# SCH_Arduino_Uno_2023-09-05.net
KiCad netlist of a schematic drawn in EasyEDA
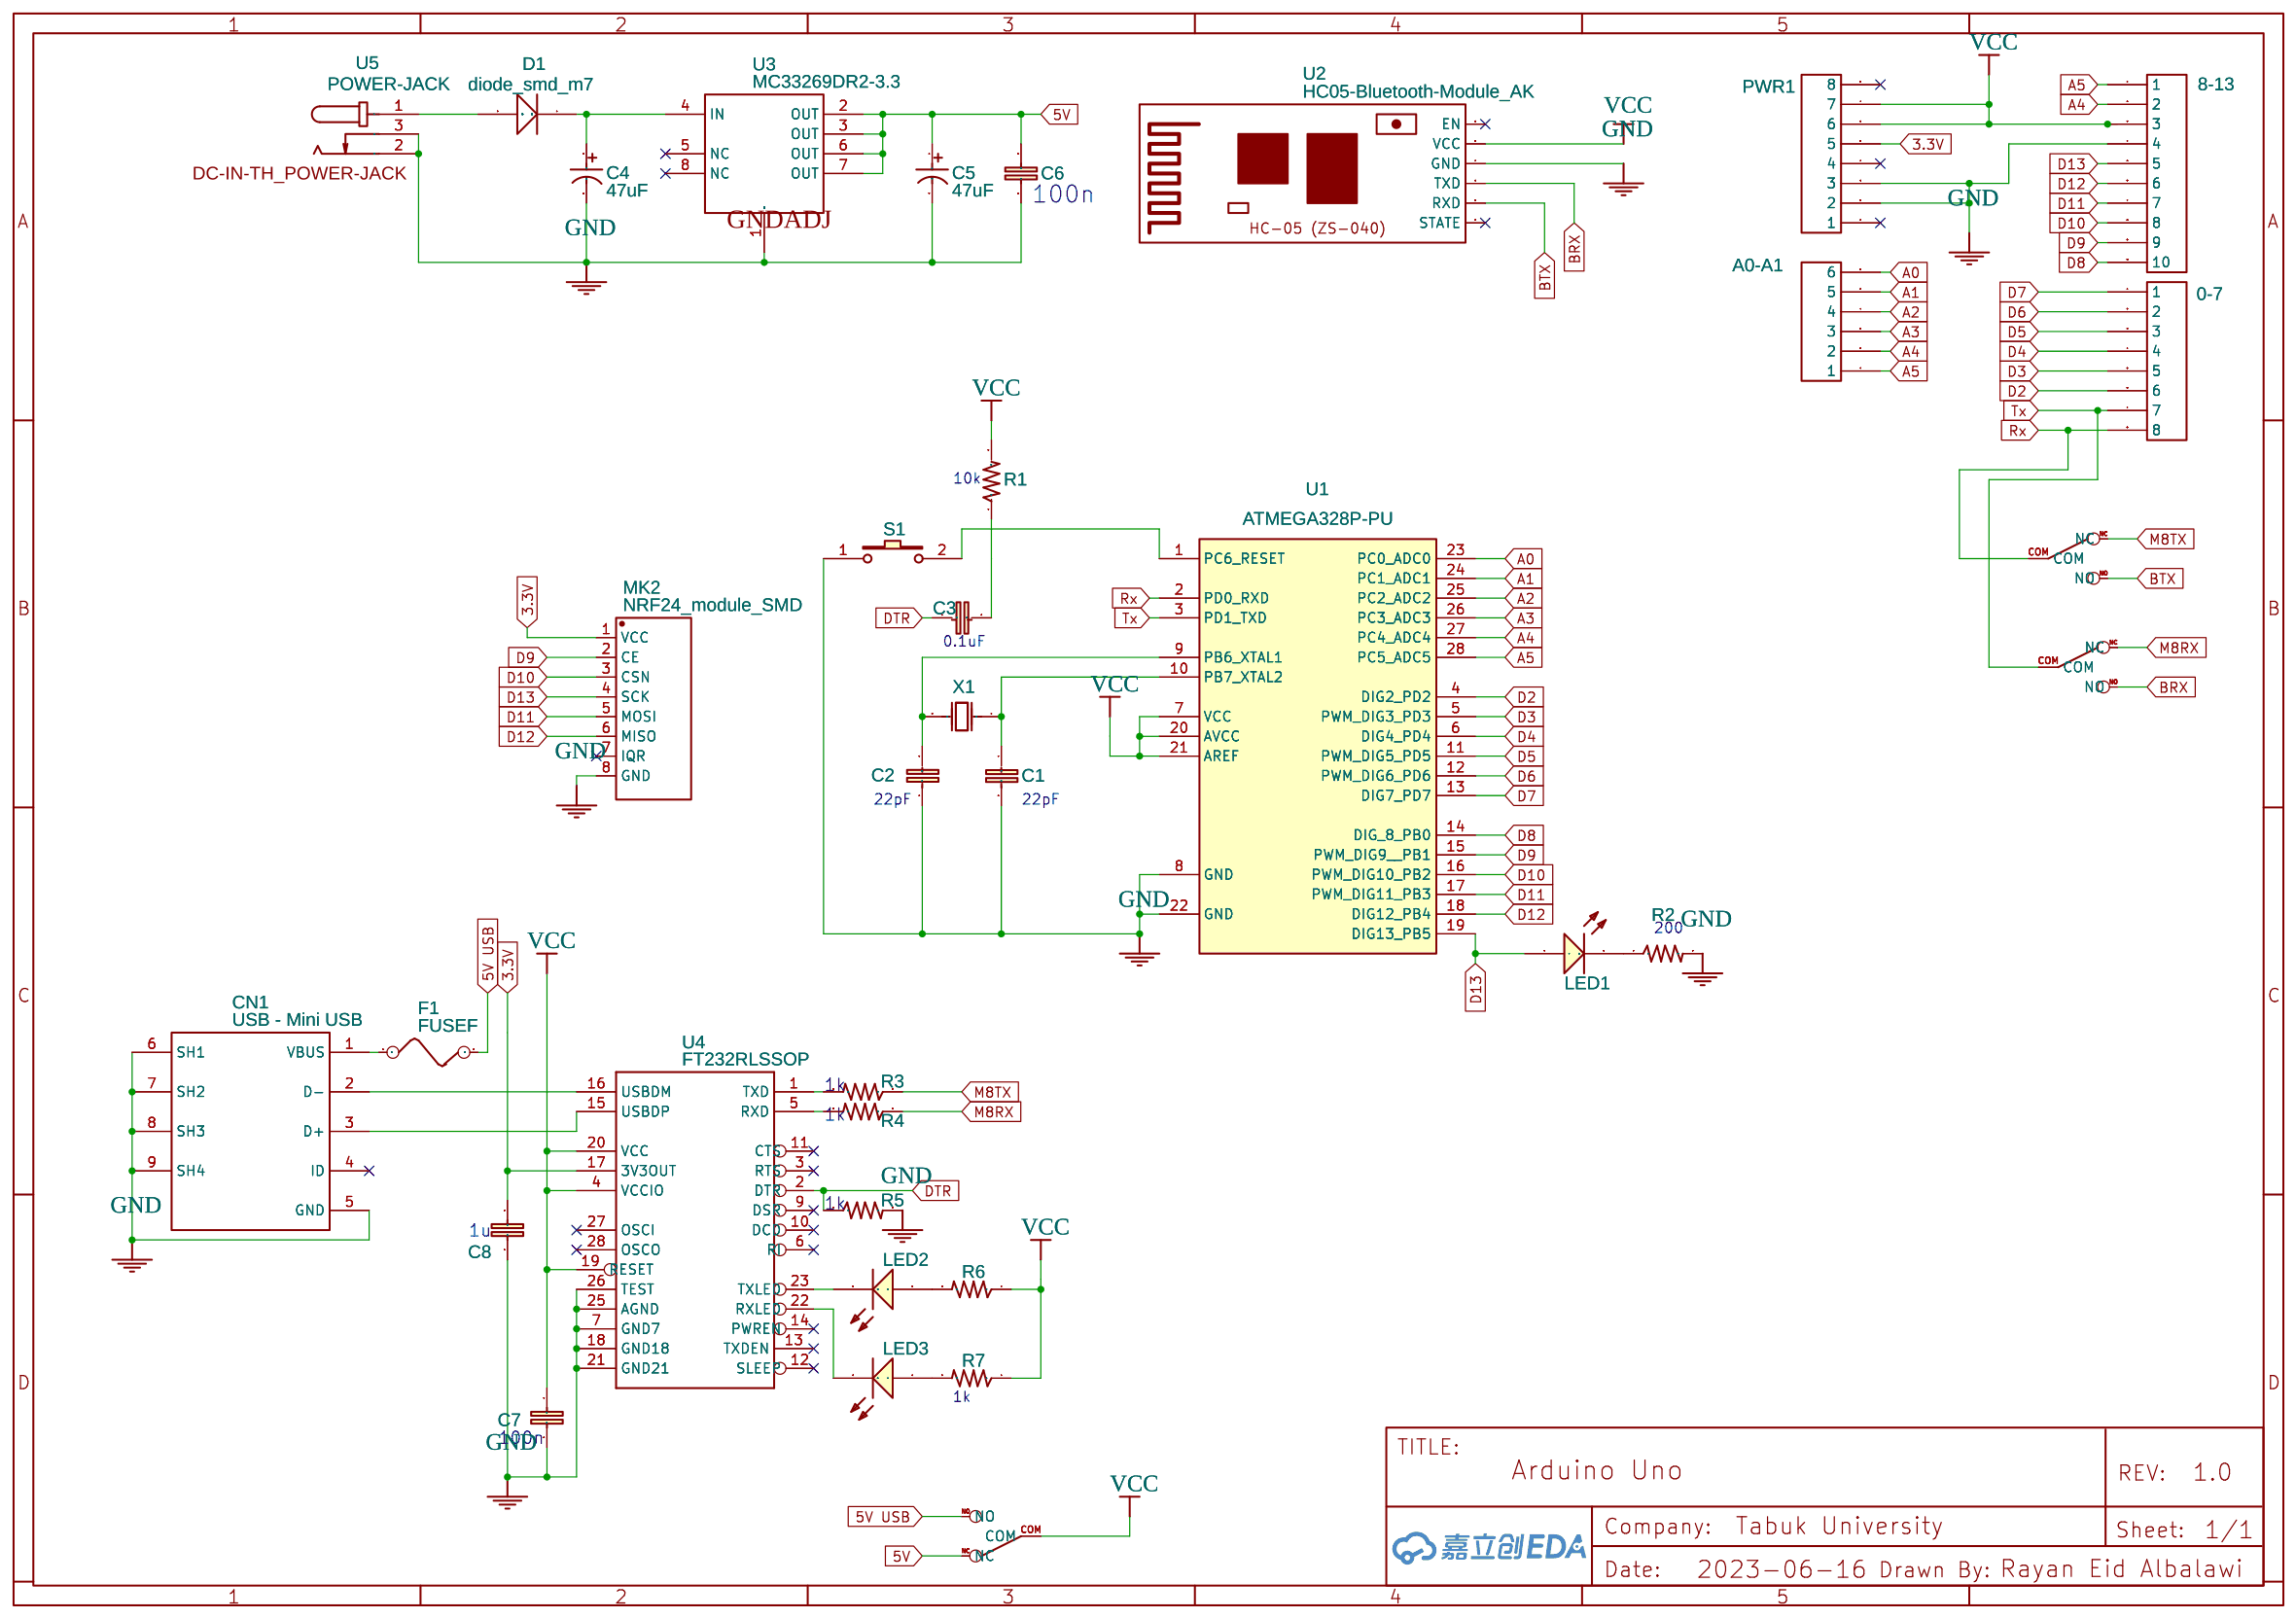
[diagram p0: schematic sheet]

(export (version "E")
  (design (tool "Eeschema 10.0.6"))
  (components
    (comp (ref "0-7")
      (value "0-7")
      (fields (field (name "Manufacturer Part") "Header2.54mm 1*8P") (field (name "Manufacturer") "ReliaPro"))
      (libsource (lib "") (part "Unknown_1070_-635"))
    )
    (comp (ref "8-13")
      (value "8-Aref")
      (fields
        (field (name "Manufacturer Part") "Headers  Pins2.54mm1*10P")
        (field (name "Manufacturer") "ReliaPro")
      )
      (libsource (lib "") (part "Unknown_1070_-730"))
    )
    (comp (ref "A0-A1")
      (value "Analogs")
      (fields
        (field (name "Manufacturer Part") "Header-Male-2.54_1x6")
        (field (name "Manufacturer") "BOOMELE")
      )
      (libsource (lib "") (part "Unknown_935_-645"))
    )
    (comp (ref "C1")
      (value "CAPACITOR_NPOL-0805")
      (fields (field (name "Manufacturer Part") "?"))
      (libsource (lib "") (part "Unknown_500_-415"))
    )
    (comp (ref "C2")
      (value "CAPACITOR_NPOL-0805")
      (fields (field (name "Manufacturer Part") "?"))
      (libsource (lib "") (part "Unknown_460_-425"))
    )
    (comp (ref "C3")
      (value "CAPACITOR_NPOL-0805")
      (fields (field (name "Manufacturer Part") "?"))
      (libsource (lib "") (part "Unknown_485_-500"))
    )
    (comp (ref "C4")
      (value "47uF")
      (fields (field (name "Manufacturer Part") "EEE-HD1C470AP") (field (name "Manufacturer") "Panasonic"))
      (libsource (lib "") (part "Unknown_290_-725"))
    )
    (comp (ref "C5")
      (value "47uF")
      (fields (field (name "Manufacturer Part") "EEE-HD1C470AP") (field (name "Manufacturer") "Panasonic"))
      (libsource (lib "") (part "Unknown_465_-725"))
    )
    (comp (ref "C6")
      (value "CAPACITOR_NPOL-0805")
      (fields (field (name "Manufacturer Part") "?"))
      (libsource (lib "") (part "Unknown_510_-720"))
    )
    (comp (ref "C7")
      (value "CAPACITOR_NPOL-0805")
      (fields (field (name "Manufacturer Part") "?"))
      (libsource (lib "") (part "Unknown_270_-90"))
    )
    (comp (ref "C8")
      (value "CAPACITOR_NPOL-0805")
      (fields (field (name "Manufacturer Part") "?"))
      (libsource (lib "") (part "Unknown_250_-185"))
    )
    (comp (ref "CN1") (value "USB - Mini USB") (libsource (lib "") (part "Unknown_120_-250")))
    (comp (ref "D1")
      (value "diode_smd_m7")
      (fields (field (name "Manufacturer Part") "?"))
      (libsource (lib "") (part "diode_smd_m7"))
    )
    (comp (ref "F1")
      (value "FUSEF")
      (fields (field (name "Manufacturer Part") "?"))
      (libsource (lib "") (part "Unknown_215_-280"))
    )
    (comp (ref "LED1")
      (value "17-21/GHC-YR1S2/3T")
      (fields (field (name "Manufacturer") "EVERLIGHT"))
      (libsource (lib "") (part "Unknown_785_-330"))
    )
    (comp (ref "LED2")
      (value "17-21/GHC-YR1S2/3T")
      (fields (field (name "Manufacturer") "EVERLIGHT"))
      (libsource (lib "") (part "Unknown_445_-160"))
    )
    (comp (ref "LED3")
      (value "17-21/GHC-YR1S2/3T")
      (fields (field (name "Manufacturer") "EVERLIGHT"))
      (libsource (lib "") (part "Unknown_445_-115"))
    )
    (comp (ref "MK2")
      (value "NRF24_module_SMD")
      (fields (field (name "Manufacturer Part") "AS01-ML01S") (field (name "Manufacturer") "Ashining"))
      (libsource (lib "") (part "Unknown_305_-480"))
    )
    (comp (ref "PWR1")
      (value "Powers")
      (fields (field (name "Manufacturer Part") "Header2.54mm 1*8P") (field (name "Manufacturer") "ReliaPro"))
      (libsource (lib "") (part "Unknown_935_-730"))
    )
    (comp (ref "R1")
      (value "0.22OHM-1_4W-1%(0805)")
      (fields (field (name "Manufacturer Part") "?"))
      (libsource (lib "") (part "Unknown_495_-570"))
    )
    (comp (ref "R2")
      (value "200")
      (fields (field (name "Manufacturer Part") "?"))
      (libsource (lib "") (part "Unknown_835_-330"))
    )
    (comp (ref "R3")
      (value "200")
      (fields (field (name "Manufacturer Part") "?"))
      (libsource (lib "") (part "Unknown_430_-260"))
    )
    (comp (ref "R4")
      (value "200")
      (fields (field (name "Manufacturer Part") "?"))
      (libsource (lib "") (part "Unknown_430_-250"))
    )
    (comp (ref "R5")
      (value "200")
      (fields (field (name "Manufacturer Part") "?"))
      (libsource (lib "") (part "Unknown_430_-200"))
    )
    (comp (ref "R6")
      (value "200")
      (fields (field (name "Manufacturer Part") "?"))
      (libsource (lib "") (part "Unknown_485_-160"))
    )
    (comp (ref "R7")
      (value "200")
      (fields (field (name "Manufacturer Part") "?"))
      (libsource (lib "") (part "Unknown_485_-115"))
    )
    (comp (ref "S1")
      (value "Button1")
      (fields (field (name "Manufacturer Part") "?"))
      (libsource (lib "") (part "Unknown_440_-530"))
    )
    (comp (ref "SW1")
      (value "SW-SLIDE")
      (fields (field (name "Manufacturer Part") "?"))
      (libsource (lib "") (part "Unknown_490_-35"))
    )
    (comp (ref "SW2")
      (value "SW-SLIDE")
      (fields (field (name "Manufacturer Part") "?"))
      (libsource (lib "") (part "Unknown_1050_-530"))
    )
    (comp (ref "SW3")
      (value "SW-SLIDE")
      (fields (field (name "Manufacturer Part") "?"))
      (libsource (lib "") (part "Unknown_1055_-475"))
    )
    (comp (ref "U1")
      (value "ATMEGA328P-PU")
      (fields (field (name "Manufacturer") "ATMEL"))
      (libsource (lib "") (part "Unknown_640_-410"))
    )
    (comp (ref "U2")
      (value "HC05-Bluetooth-Module_AK")
      (libsource (lib "") (part "HC05-Bluetooth-Module_AK"))
    )
    (comp (ref "U3")
      (value "MC33269DR2-3.3")
      (fields (field (name "Manufacturer") "ON"))
      (libsource (lib "") (part "Unknown_380_-725"))
    )
    (comp (ref "U4")
      (value "FT232RLSSOP")
      (fields (field (name "Manufacturer Part") "?"))
      (libsource (lib "") (part "Unknown_345_-190"))
    )
    (comp (ref "U5") (value "POWER-JACK") (libsource (lib "") (part "POWER-JACK")))
    (comp (ref "X1")
      (value "16MHZ")
      (fields (field (name "Manufacturer Part") "X49SD16MSD2SC") (field (name "Manufacturer") "YXC"))
      (libsource (lib "") (part "Unknown_480_-450"))
    )
  )
  (nets
    (net (code "1") (name "3.3V") (class "Default")
      (node (ref "C8") (pin "1") (pinfunction "1_1") (pintype "unspecified"))
      (node (ref "MK2") (pin "1") (pinfunction "VCC_1") (pintype "unspecified"))
      (node (ref "PWR1") (pin "5") (pinfunction "5_5") (pintype "input"))
      (node (ref "U4") (pin "17") (pinfunction "3V3OUT_17") (pintype "output"))
    )
    (net (code "2") (name "5V") (class "Default")
      (node (ref "C5") (pin "1") (pinfunction "1_1") (pintype "input"))
      (node (ref "C6") (pin "1") (pinfunction "1_1") (pintype "unspecified"))
      (node (ref "SW1") (pin "NC") (pinfunction "NC_NC") (pintype "unspecified"))
      (node (ref "U3") (pin "2") (pinfunction "OUT_2") (pintype "passive"))
      (node (ref "U3") (pin "3") (pinfunction "OUT_3") (pintype "passive"))
      (node (ref "U3") (pin "6") (pinfunction "OUT_6") (pintype "passive"))
      (node (ref "U3") (pin "7") (pinfunction "OUT_7") (pintype "passive"))
    )
    (net (code "3") (name "5V USB") (class "Default")
      (node (ref "F1") (pin "2") (pinfunction "2_2") (pintype "unspecified"))
      (node (ref "SW1") (pin "NO") (pinfunction "NO_NO") (pintype "unspecified"))
    )
    (net (code "4") (name "A0") (class "Default")
      (node (ref "A0-A1") (pin "6") (pinfunction "6_6") (pintype "input"))
      (node (ref "U1") (pin "23") (pinfunction "PC0_ADC0_23") (pintype "bidirectional"))
    )
    (net (code "5") (name "A1") (class "Default")
      (node (ref "A0-A1") (pin "5") (pinfunction "5_5") (pintype "input"))
      (node (ref "U1") (pin "24") (pinfunction "PC1_ADC1_24") (pintype "bidirectional"))
    )
    (net (code "6") (name "A2") (class "Default")
      (node (ref "A0-A1") (pin "4") (pinfunction "4_4") (pintype "input"))
      (node (ref "U1") (pin "25") (pinfunction "PC2_ADC2_25") (pintype "bidirectional"))
    )
    (net (code "7") (name "A3") (class "Default")
      (node (ref "A0-A1") (pin "3") (pinfunction "3_3") (pintype "input"))
      (node (ref "U1") (pin "26") (pinfunction "PC3_ADC3_26") (pintype "bidirectional"))
    )
    (net (code "8") (name "A4") (class "Default")
      (node (ref "8-13") (pin "2") (pinfunction "2_2") (pintype "input"))
      (node (ref "A0-A1") (pin "2") (pinfunction "2_2") (pintype "input"))
      (node (ref "U1") (pin "27") (pinfunction "PC4_ADC4_27") (pintype "bidirectional"))
    )
    (net (code "9") (name "A5") (class "Default")
      (node (ref "8-13") (pin "1") (pinfunction "1_1") (pintype "input"))
      (node (ref "A0-A1") (pin "1") (pinfunction "1_1") (pintype "input"))
      (node (ref "U1") (pin "28") (pinfunction "PC5_ADC5_28") (pintype "bidirectional"))
    )
    (net (code "10") (name "BRX") (class "Default")
      (node (ref "SW3") (pin "NO") (pinfunction "NO_NO") (pintype "unspecified"))
      (node (ref "U2") (pin "3") (pinfunction "TXD_3") (pintype "passive"))
    )
    (net (code "11") (name "BTX") (class "Default")
      (node (ref "SW2") (pin "NO") (pinfunction "NO_NO") (pintype "unspecified"))
      (node (ref "U2") (pin "2") (pinfunction "RXD_2") (pintype "passive"))
    )
    (net (code "12") (name "D2") (class "Default")
      (node (ref "0-7") (pin "6") (pinfunction "6_6") (pintype "input"))
      (node (ref "U1") (pin "4") (pinfunction "DIG2_PD2_4") (pintype "bidirectional"))
    )
    (net (code "13") (name "D3") (class "Default")
      (node (ref "0-7") (pin "5") (pinfunction "5_5") (pintype "input"))
      (node (ref "U1") (pin "5") (pinfunction "PWM_DIG3_PD3_5") (pintype "bidirectional"))
    )
    (net (code "14") (name "D4") (class "Default")
      (node (ref "0-7") (pin "4") (pinfunction "4_4") (pintype "input"))
      (node (ref "U1") (pin "6") (pinfunction "DIG4_PD4_6") (pintype "bidirectional"))
    )
    (net (code "15") (name "D5") (class "Default")
      (node (ref "0-7") (pin "3") (pinfunction "3_3") (pintype "input"))
      (node (ref "U1") (pin "11") (pinfunction "PWM_DIG5_PD5_11") (pintype "bidirectional"))
    )
    (net (code "16") (name "D6") (class "Default")
      (node (ref "0-7") (pin "2") (pinfunction "2_2") (pintype "input"))
      (node (ref "U1") (pin "12") (pinfunction "PWM_DIG6_PD6_12") (pintype "bidirectional"))
    )
    (net (code "17") (name "D7") (class "Default")
      (node (ref "0-7") (pin "1") (pinfunction "1_1") (pintype "input"))
      (node (ref "U1") (pin "13") (pinfunction "DIG7_PD7_13") (pintype "bidirectional"))
    )
    (net (code "18") (name "D8") (class "Default")
      (node (ref "8-13") (pin "10") (pinfunction "10_10") (pintype "input"))
      (node (ref "U1") (pin "14") (pinfunction "DIG_8_PB0_14") (pintype "bidirectional"))
    )
    (net (code "19") (name "D9") (class "Default")
      (node (ref "8-13") (pin "9") (pinfunction "9_9") (pintype "input"))
      (node (ref "MK2") (pin "2") (pinfunction "CE_2") (pintype "unspecified"))
      (node (ref "U1") (pin "15") (pinfunction "PWM_DIG9__PB1_15") (pintype "bidirectional"))
    )
    (net (code "20") (name "D10") (class "Default")
      (node (ref "8-13") (pin "8") (pinfunction "8_8") (pintype "input"))
      (node (ref "MK2") (pin "3") (pinfunction "CSN_3") (pintype "unspecified"))
      (node (ref "U1") (pin "16") (pinfunction "PWM_DIG10_PB2_16") (pintype "bidirectional"))
    )
    (net (code "21") (name "D11") (class "Default")
      (node (ref "8-13") (pin "7") (pinfunction "7_7") (pintype "input"))
      (node (ref "MK2") (pin "5") (pinfunction "MOSI_5") (pintype "unspecified"))
      (node (ref "U1") (pin "17") (pinfunction "PWM_DIG11_PB3_17") (pintype "bidirectional"))
    )
    (net (code "22") (name "D12") (class "Default")
      (node (ref "8-13") (pin "6") (pinfunction "6_6") (pintype "input"))
      (node (ref "MK2") (pin "6") (pinfunction "MISO_6") (pintype "unspecified"))
      (node (ref "U1") (pin "18") (pinfunction "DIG12_PB4_18") (pintype "bidirectional"))
    )
    (net (code "23") (name "D13") (class "Default")
      (node (ref "8-13") (pin "5") (pinfunction "5_5") (pintype "input"))
      (node (ref "LED1") (pin "1") (pinfunction "A_1") (pintype "input"))
      (node (ref "MK2") (pin "4") (pinfunction "SCK_4") (pintype "unspecified"))
      (node (ref "U1") (pin "19") (pinfunction "DIG13_PB5_19") (pintype "bidirectional"))
    )
    (net (code "24") (name "DTR") (class "Default")
      (node (ref "C3") (pin "1") (pinfunction "1_1") (pintype "unspecified"))
      (node (ref "R5") (pin "1") (pinfunction "1_1") (pintype "unspecified"))
      (node (ref "U4") (pin "2") (pinfunction "DTR_2") (pintype "output"))
    )
    (net (code "25") (name "GND") (class "Default")
      (node (ref "8-13") (pin "4") (pinfunction "4_4") (pintype "input"))
      (node (ref "C1") (pin "2") (pinfunction "2_2") (pintype "unspecified"))
      (node (ref "C2") (pin "1") (pinfunction "1_1") (pintype "unspecified"))
      (node (ref "C4") (pin "2") (pinfunction "2_2") (pintype "input"))
      (node (ref "C5") (pin "2") (pinfunction "2_2") (pintype "input"))
      (node (ref "C6") (pin "2") (pinfunction "2_2") (pintype "unspecified"))
      (node (ref "C7") (pin "2") (pinfunction "2_2") (pintype "unspecified"))
      (node (ref "C8") (pin "2") (pinfunction "2_2") (pintype "unspecified"))
      (node (ref "CN1") (pin "5") (pinfunction "GND_5") (pintype "passive"))
      (node (ref "CN1") (pin "6") (pinfunction "SH1_6") (pintype "passive"))
      (node (ref "CN1") (pin "7") (pinfunction "SH2_7") (pintype "passive"))
      (node (ref "CN1") (pin "8") (pinfunction "SH3_8") (pintype "passive"))
      (node (ref "CN1") (pin "9") (pinfunction "SH4_9") (pintype "passive"))
      (node (ref "MK2") (pin "8") (pinfunction "GND_8") (pintype "unspecified"))
      (node (ref "PWR1") (pin "2") (pinfunction "2_2") (pintype "input"))
      (node (ref "PWR1") (pin "3") (pinfunction "3_3") (pintype "input"))
      (node (ref "R2") (pin "2") (pinfunction "2_2") (pintype "unspecified"))
      (node (ref "R5") (pin "2") (pinfunction "2_2") (pintype "unspecified"))
      (node (ref "S1") (pin "1") (pintype "unspecified"))
      (node (ref "U1") (pin "22") (pinfunction "GND_22") (pintype "passive"))
      (node (ref "U1") (pin "8") (pinfunction "GND_8") (pintype "passive"))
      (node (ref "U2") (pin "4") (pinfunction "GND_4") (pintype "input"))
      (node (ref "U3") (pin "1") (pinfunction "GNDADJ_1") (pintype "passive"))
      (node (ref "U4") (pin "18") (pinfunction "GND18_18") (pintype "passive"))
      (node (ref "U4") (pin "21") (pinfunction "GND21_21") (pintype "passive"))
      (node (ref "U4") (pin "25") (pinfunction "AGND_25") (pintype "passive"))
      (node (ref "U4") (pin "26") (pinfunction "TEST_26") (pintype "input"))
      (node (ref "U4") (pin "7") (pinfunction "GND7_7") (pintype "passive"))
      (node (ref "U5") (pin "2") (pinfunction "2_2") (pintype "unspecified"))
      (node (ref "U5") (pin "3") (pinfunction "3_3") (pintype "unspecified"))
    )
    (net (code "26") (name "M8RX") (class "Default")
      (node (ref "R4") (pin "1") (pinfunction "1_1") (pintype "unspecified"))
      (node (ref "SW3") (pin "NC") (pinfunction "NC_NC") (pintype "unspecified"))
    )
    (net (code "27") (name "M8TX") (class "Default")
      (node (ref "R3") (pin "1") (pinfunction "1_1") (pintype "unspecified"))
      (node (ref "SW2") (pin "NC") (pinfunction "NC_NC") (pintype "unspecified"))
    )
    (net (code "28") (name "Net-(C3-Pad2)") (class "Default")
      (node (ref "C3") (pin "2") (pinfunction "2_2") (pintype "unspecified"))
      (node (ref "R1") (pin "1") (pinfunction "1_1") (pintype "unspecified"))
    )
    (net (code "29") (name "Net-(CN1-D+)") (class "Default")
      (node (ref "CN1") (pin "3") (pinfunction "D+_3") (pintype "bidirectional"))
      (node (ref "U4") (pin "15") (pinfunction "USBDP_15") (pintype "unspecified"))
    )
    (net (code "30") (name "Net-(CN1-D-)") (class "Default")
      (node (ref "CN1") (pin "2") (pinfunction "D-_2") (pintype "bidirectional"))
      (node (ref "U4") (pin "16") (pinfunction "USBDM_16") (pintype "unspecified"))
    )
    (net (code "31") (name "Net-(CN1-VBUS)") (class "Default")
      (node (ref "CN1") (pin "1") (pinfunction "VBUS_1") (pintype "passive"))
      (node (ref "F1") (pin "1") (pinfunction "1_1") (pintype "unspecified"))
    )
    (net (code "32") (name "Net-(D1-анод)") (class "Default")
      (node (ref "D1") (pin "2") (pinfunction "анод_2") (pintype "unspecified"))
      (node (ref "U5") (pin "1") (pinfunction "1_1") (pintype "unspecified"))
    )
    (net (code "33") (name "Net-(D1-катод)") (class "Default")
      (node (ref "C4") (pin "1") (pinfunction "1_1") (pintype "input"))
      (node (ref "D1") (pin "1") (pinfunction "катод_1") (pintype "unspecified"))
      (node (ref "U3") (pin "4") (pinfunction "IN_4") (pintype "passive"))
    )
    (net (code "34") (name "Net-(LED1-C)") (class "Default")
      (node (ref "LED1") (pin "2") (pinfunction "C_2") (pintype "input"))
      (node (ref "R2") (pin "1") (pinfunction "1_1") (pintype "unspecified"))
    )
    (net (code "35") (name "Net-(LED2-A)") (class "Default")
      (node (ref "LED2") (pin "1") (pinfunction "A_1") (pintype "input"))
      (node (ref "R6") (pin "2") (pinfunction "2_2") (pintype "unspecified"))
    )
    (net (code "36") (name "Net-(LED2-C)") (class "Default")
      (node (ref "LED2") (pin "2") (pinfunction "C_2") (pintype "input"))
      (node (ref "U4") (pin "23") (pinfunction "TXLED_23") (pintype "input"))
    )
    (net (code "37") (name "Net-(LED3-A)") (class "Default")
      (node (ref "LED3") (pin "1") (pinfunction "A_1") (pintype "input"))
      (node (ref "R7") (pin "2") (pinfunction "2_2") (pintype "unspecified"))
    )
    (net (code "38") (name "Net-(LED3-C)") (class "Default")
      (node (ref "LED3") (pin "2") (pinfunction "C_2") (pintype "input"))
      (node (ref "U4") (pin "22") (pinfunction "RXLED_22") (pintype "input"))
    )
    (net (code "39") (name "Net-(U1-PB6_XTAL1)") (class "Default")
      (node (ref "C2") (pin "2") (pinfunction "2_2") (pintype "unspecified"))
      (node (ref "U1") (pin "9") (pinfunction "PB6_XTAL1_9") (pintype "bidirectional"))
      (node (ref "X1") (pin "2") (pinfunction "OSC2_2") (pintype "input"))
    )
    (net (code "40") (name "Net-(U1-PB7_XTAL2)") (class "Default")
      (node (ref "C1") (pin "1") (pinfunction "1_1") (pintype "unspecified"))
      (node (ref "U1") (pin "10") (pinfunction "PB7_XTAL2_10") (pintype "bidirectional"))
      (node (ref "X1") (pin "1") (pinfunction "OSC1_1") (pintype "input"))
    )
    (net (code "41") (name "Net-(U1-PC6_RESET)") (class "Default")
      (node (ref "S1") (pin "2") (pintype "unspecified"))
      (node (ref "U1") (pin "1") (pinfunction "PC6_RESET_1") (pintype "bidirectional"))
    )
    (net (code "42") (name "Net-(U4-RXD)") (class "Default")
      (node (ref "R4") (pin "2") (pinfunction "2_2") (pintype "unspecified"))
      (node (ref "U4") (pin "5") (pinfunction "RXD_5") (pintype "input"))
    )
    (net (code "43") (name "Net-(U4-TXD)") (class "Default")
      (node (ref "R3") (pin "2") (pinfunction "2_2") (pintype "unspecified"))
      (node (ref "U4") (pin "1") (pinfunction "TXD_1") (pintype "output"))
    )
    (net (code "44") (name "Rx") (class "Default")
      (node (ref "0-7") (pin "8") (pinfunction "8_8") (pintype "input"))
      (node (ref "SW2") (pin "COM") (pinfunction "COM_COM") (pintype "unspecified"))
      (node (ref "U1") (pin "2") (pinfunction "PD0_RXD_2") (pintype "bidirectional"))
    )
    (net (code "45") (name "Tx") (class "Default")
      (node (ref "0-7") (pin "7") (pinfunction "7_7") (pintype "input"))
      (node (ref "SW3") (pin "COM") (pinfunction "COM_COM") (pintype "unspecified"))
      (node (ref "U1") (pin "3") (pinfunction "PD1_TXD_3") (pintype "bidirectional"))
    )
    (net (code "46") (name "VCC") (class "Default")
      (node (ref "8-13") (pin "3") (pinfunction "3_3") (pintype "input"))
      (node (ref "C7") (pin "1") (pinfunction "1_1") (pintype "unspecified"))
      (node (ref "PWR1") (pin "6") (pinfunction "6_6") (pintype "input"))
      (node (ref "PWR1") (pin "7") (pinfunction "7_7") (pintype "input"))
      (node (ref "R1") (pin "2") (pinfunction "2_2") (pintype "unspecified"))
      (node (ref "R6") (pin "1") (pinfunction "1_1") (pintype "unspecified"))
      (node (ref "R7") (pin "1") (pinfunction "1_1") (pintype "unspecified"))
      (node (ref "SW1") (pin "COM") (pinfunction "COM_COM") (pintype "unspecified"))
      (node (ref "U1") (pin "20") (pinfunction "AVCC_20") (pintype "passive"))
      (node (ref "U1") (pin "21") (pinfunction "AREF_21") (pintype "passive"))
      (node (ref "U1") (pin "7") (pinfunction "VCC_7") (pintype "passive"))
      (node (ref "U2") (pin "5") (pinfunction "VCC_5") (pintype "output"))
      (node (ref "U4") (pin "19") (pinfunction "RESET_19") (pintype "input"))
      (node (ref "U4") (pin "20") (pinfunction "VCC_20") (pintype "passive"))
      (node (ref "U4") (pin "4") (pinfunction "VCCIO_4") (pintype "passive"))
    )
    (net (code "47") (name "unconnected-(CN1-ID-Pad4)") (class "Default")
      (node (ref "CN1") (pin "4") (pinfunction "ID_4") (pintype "bidirectional+no_connect"))
    )
    (net (code "48") (name "unconnected-(MK2-IQR-Pad7)") (class "Default")
      (node (ref "MK2") (pin "7") (pinfunction "IQR_7") (pintype "unspecified+no_connect"))
    )
    (net (code "49") (name "unconnected-(PWR1-Pad1)") (class "Default")
      (node (ref "PWR1") (pin "1") (pinfunction "1_1") (pintype "input+no_connect"))
    )
    (net (code "50") (name "unconnected-(PWR1-Pad4)") (class "Default")
      (node (ref "PWR1") (pin "4") (pinfunction "4_4") (pintype "input+no_connect"))
    )
    (net (code "51") (name "unconnected-(PWR1-Pad8)") (class "Default")
      (node (ref "PWR1") (pin "8") (pinfunction "8_8") (pintype "input+no_connect"))
    )
    (net (code "52") (name "unconnected-(U2-EN-Pad6)") (class "Default")
      (node (ref "U2") (pin "6") (pinfunction "EN_6") (pintype "bidirectional+no_connect"))
    )
    (net (code "53") (name "unconnected-(U2-STATE-Pad1)") (class "Default")
      (node (ref "U2") (pin "1") (pinfunction "STATE_1") (pintype "passive+no_connect"))
    )
    (net (code "54") (name "unconnected-(U3-NC-Pad5)") (class "Default")
      (node (ref "U3") (pin "5") (pinfunction "NC_5") (pintype "unspecified+no_connect"))
    )
    (net (code "55") (name "unconnected-(U3-NC-Pad8)") (class "Default")
      (node (ref "U3") (pin "8") (pinfunction "NC_8") (pintype "unspecified+no_connect"))
    )
    (net (code "56") (name "unconnected-(U4-CTS-Pad11)") (class "Default")
      (node (ref "U4") (pin "11") (pinfunction "CTS_11") (pintype "input+no_connect"))
    )
    (net (code "57") (name "unconnected-(U4-DCD-Pad10)") (class "Default")
      (node (ref "U4") (pin "10") (pinfunction "DCD_10") (pintype "input+no_connect"))
    )
    (net (code "58") (name "unconnected-(U4-DSR-Pad9)") (class "Default")
      (node (ref "U4") (pin "9") (pinfunction "DSR_9") (pintype "input+no_connect"))
    )
    (net (code "59") (name "unconnected-(U4-OSCI-Pad27)") (class "Default")
      (node (ref "U4") (pin "27") (pinfunction "OSCI_27") (pintype "input+no_connect"))
    )
    (net (code "60") (name "unconnected-(U4-OSCO-Pad28)") (class "Default")
      (node (ref "U4") (pin "28") (pinfunction "OSCO_28") (pintype "output+no_connect"))
    )
    (net (code "61") (name "unconnected-(U4-PWREN-Pad14)") (class "Default")
      (node (ref "U4") (pin "14") (pinfunction "PWREN_14") (pintype "input+no_connect"))
    )
    (net (code "62") (name "unconnected-(U4-RI-Pad6)") (class "Default")
      (node (ref "U4") (pin "6") (pinfunction "RI_6") (pintype "input+no_connect"))
    )
    (net (code "63") (name "unconnected-(U4-RTS-Pad3)") (class "Default")
      (node (ref "U4") (pin "3") (pinfunction "RTS_3") (pintype "output+no_connect"))
    )
    (net (code "64") (name "unconnected-(U4-SLEEP-Pad12)") (class "Default")
      (node (ref "U4") (pin "12") (pinfunction "SLEEP_12") (pintype "input+no_connect"))
    )
    (net (code "65") (name "unconnected-(U4-TXDEN-Pad13)") (class "Default")
      (node (ref "U4") (pin "13") (pinfunction "TXDEN_13") (pintype "input+no_connect"))
    )
  )
)
